# DebugCircuit.net
KiCad netlist of a schematic drawn in Altium Designer
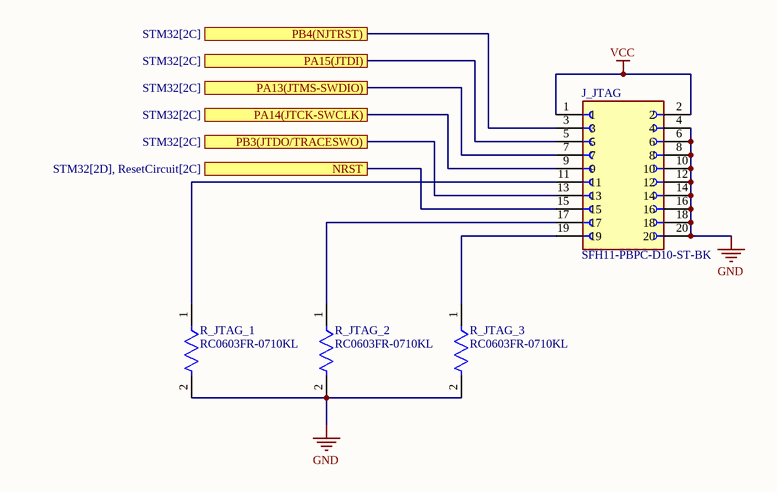
[diagram p0: DebugCircuit.SchDoc]

(export (version "E")
  (design (tool "Eeschema 10.0.6"))
  (components
    (comp (ref "J_JTAG")
      (value "SFH11-PBPC-D10-ST-BK")
      (footprint "SULLINS_SFH11-PBPC-D10-ST-BK")
      (description "20 Position Header Connector 0.100 (2.54mm) Through Hole Gold")
      (fields (field (name "MF") "Sullins Connector"))
      (libsource (lib "SFH11-PBPC-D10-ST-BK") (part "SFH11-PBPC-D10-ST-BK"))
    )
    (comp (ref "R_JTAG_1")
      (value "RC0603FR-0710KL")
      (footprint "FP-RC0603-0_55-IPC_C")
      (description "RES 10K OHM 1% 1/10W 0603")
      (fields (field (name "TOLERANCE") "1%"))
      (libsource (lib "Altium Content Vault") (part "1029c3af85768c4190bb7ad29bc67b5"))
    )
    (comp (ref "R_JTAG_2")
      (value "RC0603FR-0710KL")
      (footprint "FP-RC0603-0_55-IPC_C")
      (description "RES 10K OHM 1% 1/10W 0603")
      (fields (field (name "TOLERANCE") "1%"))
      (libsource (lib "Altium Content Vault") (part "1029c3af85768c4190bb7ad29bc67b5"))
    )
    (comp (ref "R_JTAG_3")
      (value "RC0603FR-0710KL")
      (footprint "FP-RC0603-0_55-IPC_C")
      (description "RES 10K OHM 1% 1/10W 0603")
      (fields (field (name "TOLERANCE") "1%"))
      (libsource (lib "Altium Content Vault") (part "1029c3af85768c4190bb7ad29bc67b5"))
    )
  )
  (nets
    (net (code "1") (name "/NRST") (class "Default")
      (node (ref "J_JTAG") (pin "15") (pinfunction "15_15") (pintype "passive"))
    )
    (net (code "2") (name "/PA13(JTMS-SWDIO)") (class "Default")
      (node (ref "J_JTAG") (pin "7") (pinfunction "7_7") (pintype "passive"))
    )
    (net (code "3") (name "/PA14(JTCK-SWCLK)") (class "Default")
      (node (ref "J_JTAG") (pin "9") (pinfunction "9_9") (pintype "passive"))
    )
    (net (code "4") (name "/PA15(JTDI)") (class "Default")
      (node (ref "J_JTAG") (pin "5") (pinfunction "5_5") (pintype "passive"))
    )
    (net (code "5") (name "/PB3(JTDO{slash}TRACESWO)") (class "Default")
      (node (ref "J_JTAG") (pin "13") (pinfunction "13_13") (pintype "passive"))
    )
    (net (code "6") (name "/PB4(NJTRST)") (class "Default")
      (node (ref "J_JTAG") (pin "3") (pinfunction "3_3") (pintype "passive"))
    )
    (net (code "7") (name "GND") (class "Default")
      (node (ref "J_JTAG") (pin "10") (pinfunction "10_10") (pintype "passive"))
      (node (ref "J_JTAG") (pin "12") (pinfunction "12_12") (pintype "passive"))
      (node (ref "J_JTAG") (pin "14") (pinfunction "14_14") (pintype "passive"))
      (node (ref "J_JTAG") (pin "16") (pinfunction "16_16") (pintype "passive"))
      (node (ref "J_JTAG") (pin "18") (pinfunction "18_18") (pintype "passive"))
      (node (ref "J_JTAG") (pin "20") (pinfunction "20_20") (pintype "passive"))
      (node (ref "J_JTAG") (pin "4") (pinfunction "4_4") (pintype "passive"))
      (node (ref "J_JTAG") (pin "6") (pinfunction "6_6") (pintype "passive"))
      (node (ref "J_JTAG") (pin "8") (pinfunction "8_8") (pintype "passive"))
      (node (ref "R_JTAG_1") (pin "2") (pinfunction "2_2") (pintype "passive"))
      (node (ref "R_JTAG_2") (pin "2") (pinfunction "2_2") (pintype "passive"))
      (node (ref "R_JTAG_3") (pin "2") (pinfunction "2_2") (pintype "passive"))
    )
    (net (code "8") (name "Net-(J_JTAG-Pad11)") (class "Default")
      (node (ref "J_JTAG") (pin "11") (pinfunction "11_11") (pintype "passive"))
      (node (ref "R_JTAG_1") (pin "1") (pinfunction "1_1") (pintype "passive"))
    )
    (net (code "9") (name "Net-(J_JTAG-Pad17)") (class "Default")
      (node (ref "J_JTAG") (pin "17") (pinfunction "17_17") (pintype "passive"))
      (node (ref "R_JTAG_2") (pin "1") (pinfunction "1_1") (pintype "passive"))
    )
    (net (code "10") (name "Net-(J_JTAG-Pad19)") (class "Default")
      (node (ref "J_JTAG") (pin "19") (pinfunction "19_19") (pintype "passive"))
      (node (ref "R_JTAG_3") (pin "1") (pinfunction "1_1") (pintype "passive"))
    )
    (net (code "11") (name "VCC") (class "Default")
      (node (ref "J_JTAG") (pin "1") (pinfunction "1_1") (pintype "passive"))
      (node (ref "J_JTAG") (pin "2") (pinfunction "2_2") (pintype "passive"))
    )
  )
)
